# microB.net
KiCad netlist of a schematic drawn in Altium Designer
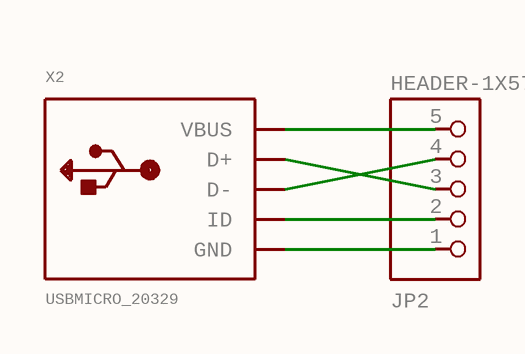
[diagram p0: microB.SchDoc]

(export (version "E")
  (design (tool "Eeschema 10.0.6"))
  (components
    (comp (ref "JP2")
      (value "HEADER-1X570MIL")
      (footprint "1X05_ROUND_70")
      (description "PIN HEADER")
      (libsource (lib "microbuilder") (part "HEADER-1X570MIL"))
    )
    (comp (ref "X2")
      (value "USBMICRO_20329")
      (footprint "4UCONN_20329")
      (description "USB ConnectorsUSBMINIB - Surface Mount Female Mini-B USB Connector    4UConnector: 06564")
      (libsource (lib "microbuilder") (part "USBMICRO_20329"))
    )
  )
  (nets
    (net (code "1") (name "Net-(JP2-Pad2)") (class "Default")
      (node (ref "JP2") (pin "2") (pinfunction "2_2") (pintype "passive"))
      (node (ref "X2") (pin "ID") (pinfunction "ID_ID") (pintype "bidirectional"))
    )
    (net (code "2") (name "Net-(JP2-Pad3)") (class "Default")
      (node (ref "JP2") (pin "3") (pinfunction "3_3") (pintype "passive"))
      (node (ref "X2") (pin "D+") (pinfunction "D+_D+") (pintype "bidirectional"))
    )
    (net (code "3") (name "Net-(JP2-Pad4)") (class "Default")
      (node (ref "JP2") (pin "4") (pinfunction "4_4") (pintype "passive"))
      (node (ref "X2") (pin "D-") (pinfunction "D-_D-") (pintype "bidirectional"))
    )
    (net (code "4") (name "Net-(JP2-Pad5)") (class "Default")
      (node (ref "JP2") (pin "5") (pinfunction "5_5") (pintype "passive"))
      (node (ref "X2") (pin "VBUS") (pinfunction "VBUS_VBUS") (pintype "power_in"))
    )
    (net (code "5") (name "Net-(X2-GND)") (class "Default")
      (node (ref "JP2") (pin "1") (pinfunction "1_1") (pintype "passive"))
      (node (ref "X2") (pin "BASE@1_BASE@2_GND_SPRT@1_SPRT@2_SPRT@3_SPRT@4") (pinfunction "GND_BASE@1_BASE@2_GND_SPRT@1_SPRT@2_SPRT@3_SPRT@4") (pintype "power_in"))
    )
  )
)
